# Relay_MCU.net
KiCad netlist of a schematic drawn in Altium Designer
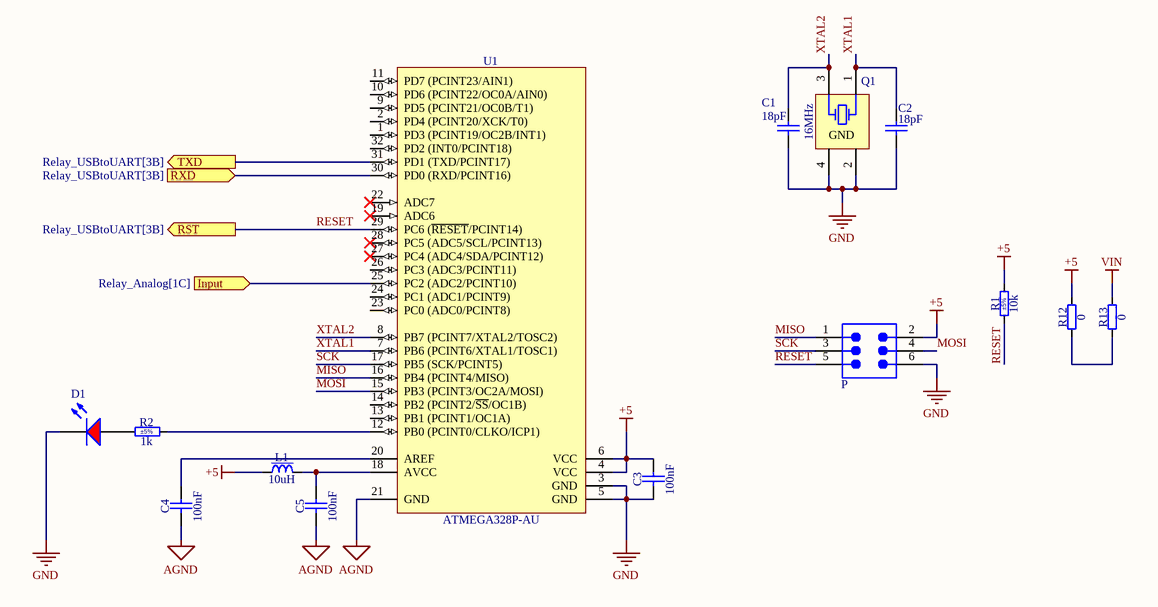
[diagram p0: Relay_MCU.SchDoc]

(export (version "E")
  (design (tool "Eeschema 10.0.6"))
  (components
    (comp (ref "C1")
      (value "18pF")
      (footprint "CAPC2012X135N")
      (description "Non-polarised capacitor")
      (fields
        (field (name "PART NUMBER") "CC0805_18PF_50V_5%_NP0")
        (field (name "VOLTAGE") "50V")
        (field (name "AUTHOR") "CERN DEM JLC")
      )
      (libsource (lib "Capacitors") (part "Capacitor - non polarized"))
    )
    (comp (ref "C2")
      (value "18pF")
      (footprint "CAPC2012X135N")
      (description "Non-polarised capacitor")
      (fields
        (field (name "PART NUMBER") "CC0805_18PF_50V_5%_NP0")
        (field (name "VOLTAGE") "50V")
        (field (name "AUTHOR") "CERN DEM JLC")
      )
      (libsource (lib "Capacitors") (part "Capacitor - non polarized"))
    )
    (comp (ref "C3")
      (value "100nF")
      (footprint "CAPC2012X135N")
      (description "Non-polarised capacitor")
      (fields
        (field (name "PART NUMBER") "CC0805_100NF_50V_10%_X7R")
        (field (name "VOLTAGE") "50V")
        (field (name "AUTHOR") "CERN DEM JLC")
      )
      (libsource (lib "Capacitors") (part "Capacitor - non polarized"))
    )
    (comp (ref "C4")
      (value "100nF")
      (footprint "CAPC2012X135N")
      (description "Non-polarised capacitor")
      (fields
        (field (name "PART NUMBER") "CC0805_100NF_50V_10%_X7R")
        (field (name "VOLTAGE") "50V")
        (field (name "AUTHOR") "CERN DEM JLC")
      )
      (libsource (lib "Capacitors") (part "Capacitor - non polarized"))
    )
    (comp (ref "C5")
      (value "100nF")
      (footprint "CAPC2012X135N")
      (description "Non-polarised capacitor")
      (fields
        (field (name "PART NUMBER") "CC0805_100NF_50V_10%_X7R")
        (field (name "VOLTAGE") "50V")
        (field (name "AUTHOR") "CERN DEM JLC")
      )
      (libsource (lib "Capacitors") (part "Capacitor - non polarized"))
    )
    (comp (ref "D1")
      (value "Red, 2V, 140°")
      (footprint "WL-SMCW_0805_150080xx75000")
      (description "WL-SMCW Mono-color Chip LED Waterclear, size 0805, Red, 2V, 140°")
      (fields
        (field (name "MANUFACTURER PART NUMBER") "150080RS75000")
        (field (name "MANUFACTURER") "Wurth Elektronik")
      )
      (libsource (lib "WE - Optoelectronic Components") (part "LED_Red_2A-1K"))
    )
    (comp (ref "L1")
      (value "10uH")
      (footprint "INDC2014X145N")
      (description "Inductor With Core")
      (fields
        (field (name "PART NUMBER") "IND0805_10UH_5%_EPCOS_B82498B")
        (field (name "POWER") "700mA")
        (field (name "AUTHOR") "CERN DEM JLC")
      )
      (libsource (lib "Inductors & Transformers") (part "Inductor With Magnetic core"))
    )
    (comp (ref "P")
      (value "61300621121")
      (footprint "61300621121")
      (description "WR-PHD Pin Header, THT, Vertical, pitch 2.54mm, 2 Row, 6P")
      (fields (field (name "MANUFACTURER") "Wurth Elektronik"))
      (libsource (lib "Altium_WR-PHD (rev24a)") (part "61300621121"))
    )
    (comp (ref "Q1")
      (value "16MHz")
      (footprint "XTAL_EPSON_TSX-3225")
      (description "Crystal 4 pins 1=XTAL Control 2=GND3=XTAL 4=GND")
      (fields
        (field (name "PART NUMBER") "XTAL_16MHZ_EPSON_TSX-3225 40.0000MF10Z-B6")
        (field (name "MANUFACTURER") "EPSON")
        (field (name "AUTHOR") "CERN DEM HF")
      )
      (libsource (lib "ICs And Semiconductors") (part "Quartz Crystal 1X 2GND 3X 4GND"))
    )
    (comp (ref "R1")
      (value "10k")
      (footprint "RESC2012X60N")
      (description "Resistor - 5%")
      (fields
        (field (name "TOLERANCE") "±5%")
        (field (name "PART NUMBER") "R0805_10K_5%_0.125W_100PPM")
        (field (name "POWER") "0.125W")
        (field (name "AUTHOR") "CERN DEM JLC")
      )
      (libsource (lib "Resistors") (part "Resistor - 1%"))
    )
    (comp (ref "R2")
      (value "1k")
      (footprint "RESC2012X60N")
      (description "Resistor - 5%")
      (fields
        (field (name "TOLERANCE") "±5%")
        (field (name "PART NUMBER") "R0805_1K_5%_0.125W_100PPM")
        (field (name "POWER") "0.125W")
        (field (name "AUTHOR") "CERN DEM JLC")
      )
      (libsource (lib "Resistors") (part "Resistor - 1%"))
    )
    (comp (ref "R12")
      (value "0")
      (footprint "RESC2012X60N")
      (description "Resistor")
      (fields
        (field (name "PART NUMBER") "R0805_0R_JUMPER")
        (field (name "MANUFACTURER") "GENERIC")
        (field (name "AUTHOR") "CERN DEM JLC")
      )
      (libsource (lib "Resistors") (part "Resistor"))
    )
    (comp (ref "R13")
      (value "0")
      (footprint "RESC2012X60N")
      (description "Resistor")
      (fields
        (field (name "PART NUMBER") "R0805_0R_JUMPER")
        (field (name "MANUFACTURER") "GENERIC")
        (field (name "AUTHOR") "CERN DEM JLC")
      )
      (libsource (lib "Resistors") (part "Resistor"))
    )
    (comp (ref "U1")
      (value "ATMEGA328P-AU")
      (footprint "QFP80P900X900X120-32N")
      (description "8-bit AVR Microcontroller, 32KB Flash, 1KB EEPROM, 2KB SRAM, 32-Pin TQFP")
      (fields (field (name "MANUFACTURER") "ATMEL") (field (name "AUTHOR") "CERN DEM JLC"))
      (libsource (lib "ICs And Semiconductors") (part "ATMEGA328P-AU"))
    )
  )
  (nets
    (net (code "1") (name "+5") (class "Default")
      (node (ref "C3") (pin "2") (pinfunction "2_2") (pintype "passive"))
      (node (ref "L1") (pin "1") (pinfunction "1_1") (pintype "passive"))
      (node (ref "P") (pin "2") (pinfunction "2_2") (pintype "passive"))
      (node (ref "R1") (pin "2") (pinfunction "2_2") (pintype "passive"))
      (node (ref "R12") (pin "2") (pinfunction "2_2") (pintype "passive"))
      (node (ref "U1") (pin "4") (pinfunction "VCC_4") (pintype "power_in"))
      (node (ref "U1") (pin "6") (pinfunction "VCC_6") (pintype "power_in"))
    )
    (net (code "2") (name "/Input") (class "Default")
      (node (ref "U1") (pin "25") (pinfunction "PC2_(ADC2/PCINT10)_25") (pintype "bidirectional"))
    )
    (net (code "3") (name "/MISO") (class "Default")
      (node (ref "P") (pin "1") (pinfunction "1_1") (pintype "passive"))
      (node (ref "U1") (pin "16") (pinfunction "PB4_(PCINT4/MISO)_16") (pintype "bidirectional"))
    )
    (net (code "4") (name "/MOSI") (class "Default")
      (node (ref "P") (pin "4") (pinfunction "4_4") (pintype "passive"))
      (node (ref "U1") (pin "15") (pinfunction "PB3_(PCINT3/OC2A/MOSI)_15") (pintype "bidirectional"))
    )
    (net (code "5") (name "/RESET") (class "Default")
      (node (ref "P") (pin "5") (pinfunction "5_5") (pintype "passive"))
      (node (ref "R1") (pin "1") (pinfunction "1_1") (pintype "passive"))
      (node (ref "U1") (pin "29") (pinfunction "PC6_(~{RESET}/PCINT14)_29") (pintype "bidirectional"))
    )
    (net (code "6") (name "/RXD") (class "Default")
      (node (ref "U1") (pin "30") (pinfunction "PD0_(RXD/PCINT16)_30") (pintype "bidirectional"))
    )
    (net (code "7") (name "/SCK") (class "Default")
      (node (ref "P") (pin "3") (pinfunction "3_3") (pintype "passive"))
      (node (ref "U1") (pin "17") (pinfunction "PB5_(SCK/PCINT5)_17") (pintype "bidirectional"))
    )
    (net (code "8") (name "/TXD") (class "Default")
      (node (ref "U1") (pin "31") (pinfunction "PD1_(TXD/PCINT17)_31") (pintype "bidirectional"))
    )
    (net (code "9") (name "/XTAL1") (class "Default")
      (node (ref "C2") (pin "1") (pinfunction "1_1") (pintype "passive"))
      (node (ref "Q1") (pin "1") (pinfunction "X_1") (pintype "passive"))
      (node (ref "U1") (pin "7") (pinfunction "PB6_(PCINT6/XTAL1/TOSC1)_7") (pintype "bidirectional"))
    )
    (net (code "10") (name "/XTAL2") (class "Default")
      (node (ref "C1") (pin "2") (pinfunction "2_2") (pintype "passive"))
      (node (ref "Q1") (pin "3") (pinfunction "X_3") (pintype "passive"))
      (node (ref "U1") (pin "8") (pinfunction "PB7_(PCINT7/XTAL2/TOSC2)_8") (pintype "bidirectional"))
    )
    (net (code "11") (name "AGND") (class "Default")
      (node (ref "C4") (pin "1") (pinfunction "1_1") (pintype "passive"))
      (node (ref "C5") (pin "1") (pinfunction "1_1") (pintype "passive"))
      (node (ref "U1") (pin "21") (pinfunction "GND_21") (pintype "power_in"))
    )
    (net (code "12") (name "GND") (class "Default")
      (node (ref "C1") (pin "1") (pinfunction "1_1") (pintype "passive"))
      (node (ref "C2") (pin "2") (pinfunction "2_2") (pintype "passive"))
      (node (ref "C3") (pin "1") (pinfunction "1_1") (pintype "passive"))
      (node (ref "D1") (pin "1") (pinfunction "K_1") (pintype "passive"))
      (node (ref "P") (pin "6") (pinfunction "6_6") (pintype "passive"))
      (node (ref "Q1") (pin "2") (pinfunction "GND_2") (pintype "power_in"))
      (node (ref "Q1") (pin "4") (pinfunction "GND_4") (pintype "power_in"))
      (node (ref "U1") (pin "3") (pinfunction "GND_3") (pintype "power_in"))
      (node (ref "U1") (pin "5") (pinfunction "GND_5") (pintype "power_in"))
    )
    (net (code "13") (name "Net-(D1-A)") (class "Default")
      (node (ref "D1") (pin "2") (pinfunction "A_2") (pintype "passive"))
      (node (ref "R2") (pin "1") (pinfunction "1_1") (pintype "passive"))
    )
    (net (code "14") (name "Net-(R12-Pad1)") (class "Default")
      (node (ref "R12") (pin "1") (pinfunction "1_1") (pintype "passive"))
      (node (ref "R13") (pin "1") (pinfunction "1_1") (pintype "passive"))
    )
    (net (code "15") (name "Net-(U1-AREF)") (class "Default")
      (node (ref "C4") (pin "2") (pinfunction "2_2") (pintype "passive"))
      (node (ref "U1") (pin "20") (pinfunction "AREF_20") (pintype "passive"))
    )
    (net (code "16") (name "Net-(U1-AVCC)") (class "Default")
      (node (ref "C5") (pin "2") (pinfunction "2_2") (pintype "passive"))
      (node (ref "L1") (pin "2") (pinfunction "2_2") (pintype "passive"))
      (node (ref "U1") (pin "18") (pinfunction "AVCC_18") (pintype "power_in"))
    )
    (net (code "17") (name "Net-(U1-PB0_(PCINT0{slash}CLKO{slash}ICP1))") (class "Default")
      (node (ref "R2") (pin "2") (pinfunction "2_2") (pintype "passive"))
      (node (ref "U1") (pin "12") (pinfunction "PB0_(PCINT0/CLKO/ICP1)_12") (pintype "bidirectional"))
    )
    (net (code "18") (name "VIN") (class "Default")
      (node (ref "R13") (pin "2") (pinfunction "2_2") (pintype "passive"))
    )
    (net (code "19") (name "unconnected-(U1-ADC6-Pad19)") (class "Default")
      (node (ref "U1") (pin "19") (pinfunction "ADC6_19") (pintype "input+no_connect"))
    )
    (net (code "20") (name "unconnected-(U1-ADC7-Pad22)") (class "Default")
      (node (ref "U1") (pin "22") (pinfunction "ADC7_22") (pintype "input+no_connect"))
    )
    (net (code "21") (name "unconnected-(U1-PB1_(PCINT1{slash}OC1A)-Pad13)") (class "Default")
      (node (ref "U1") (pin "13") (pinfunction "PB1_(PCINT1/OC1A)_13") (pintype "bidirectional"))
    )
    (net (code "22") (name "unconnected-(U1-PB2_(PCINT2{slash}~{SS}{slash}OC1B)-Pad14)") (class "Default")
      (node (ref "U1") (pin "14") (pinfunction "PB2_(PCINT2/~{SS}/OC1B)_14") (pintype "bidirectional"))
    )
    (net (code "23") (name "unconnected-(U1-PC0_(ADC0{slash}PCINT8)-Pad23)") (class "Default")
      (node (ref "U1") (pin "23") (pinfunction "PC0_(ADC0/PCINT8)_23") (pintype "bidirectional"))
    )
    (net (code "24") (name "unconnected-(U1-PC1_(ADC1{slash}PCINT9)-Pad24)") (class "Default")
      (node (ref "U1") (pin "24") (pinfunction "PC1_(ADC1/PCINT9)_24") (pintype "bidirectional"))
    )
    (net (code "25") (name "unconnected-(U1-PC3_(ADC3{slash}PCINT11)-Pad26)") (class "Default")
      (node (ref "U1") (pin "26") (pinfunction "PC3_(ADC3/PCINT11)_26") (pintype "bidirectional"))
    )
    (net (code "26") (name "unconnected-(U1-PC4_(ADC4{slash}SDA{slash}PCINT12)-Pad27)") (class "Default")
      (node (ref "U1") (pin "27") (pinfunction "PC4_(ADC4/SDA/PCINT12)_27") (pintype "bidirectional+no_connect"))
    )
    (net (code "27") (name "unconnected-(U1-PC5_(ADC5{slash}SCL{slash}PCINT13)-Pad28)") (class "Default")
      (node (ref "U1") (pin "28") (pinfunction "PC5_(ADC5/SCL/PCINT13)_28") (pintype "bidirectional+no_connect"))
    )
    (net (code "28") (name "unconnected-(U1-PD2_(INT0{slash}PCINT18)-Pad32)") (class "Default")
      (node (ref "U1") (pin "32") (pinfunction "PD2_(INT0/PCINT18)_32") (pintype "bidirectional"))
    )
    (net (code "29") (name "unconnected-(U1-PD3_(PCINT19{slash}OC2B{slash}INT1)-Pad1)") (class "Default")
      (node (ref "U1") (pin "1") (pinfunction "PD3_(PCINT19/OC2B/INT1)_1") (pintype "bidirectional"))
    )
    (net (code "30") (name "unconnected-(U1-PD4_(PCINT20{slash}XCK{slash}T0)-Pad2)") (class "Default")
      (node (ref "U1") (pin "2") (pinfunction "PD4_(PCINT20/XCK/T0)_2") (pintype "bidirectional"))
    )
    (net (code "31") (name "unconnected-(U1-PD5_(PCINT21{slash}OC0B{slash}T1)-Pad9)") (class "Default")
      (node (ref "U1") (pin "9") (pinfunction "PD5_(PCINT21/OC0B/T1)_9") (pintype "bidirectional"))
    )
    (net (code "32") (name "unconnected-(U1-PD6_(PCINT22{slash}OC0A{slash}AIN0)-Pad10)") (class "Default")
      (node (ref "U1") (pin "10") (pinfunction "PD6_(PCINT22/OC0A/AIN0)_10") (pintype "bidirectional"))
    )
    (net (code "33") (name "unconnected-(U1-PD7_(PCINT23{slash}AIN1)-Pad11)") (class "Default")
      (node (ref "U1") (pin "11") (pinfunction "PD7_(PCINT23/AIN1)_11") (pintype "bidirectional"))
    )
  )
)
